# External_Trigger_Buffer.net
KiCad netlist of a schematic drawn in Altium Designer
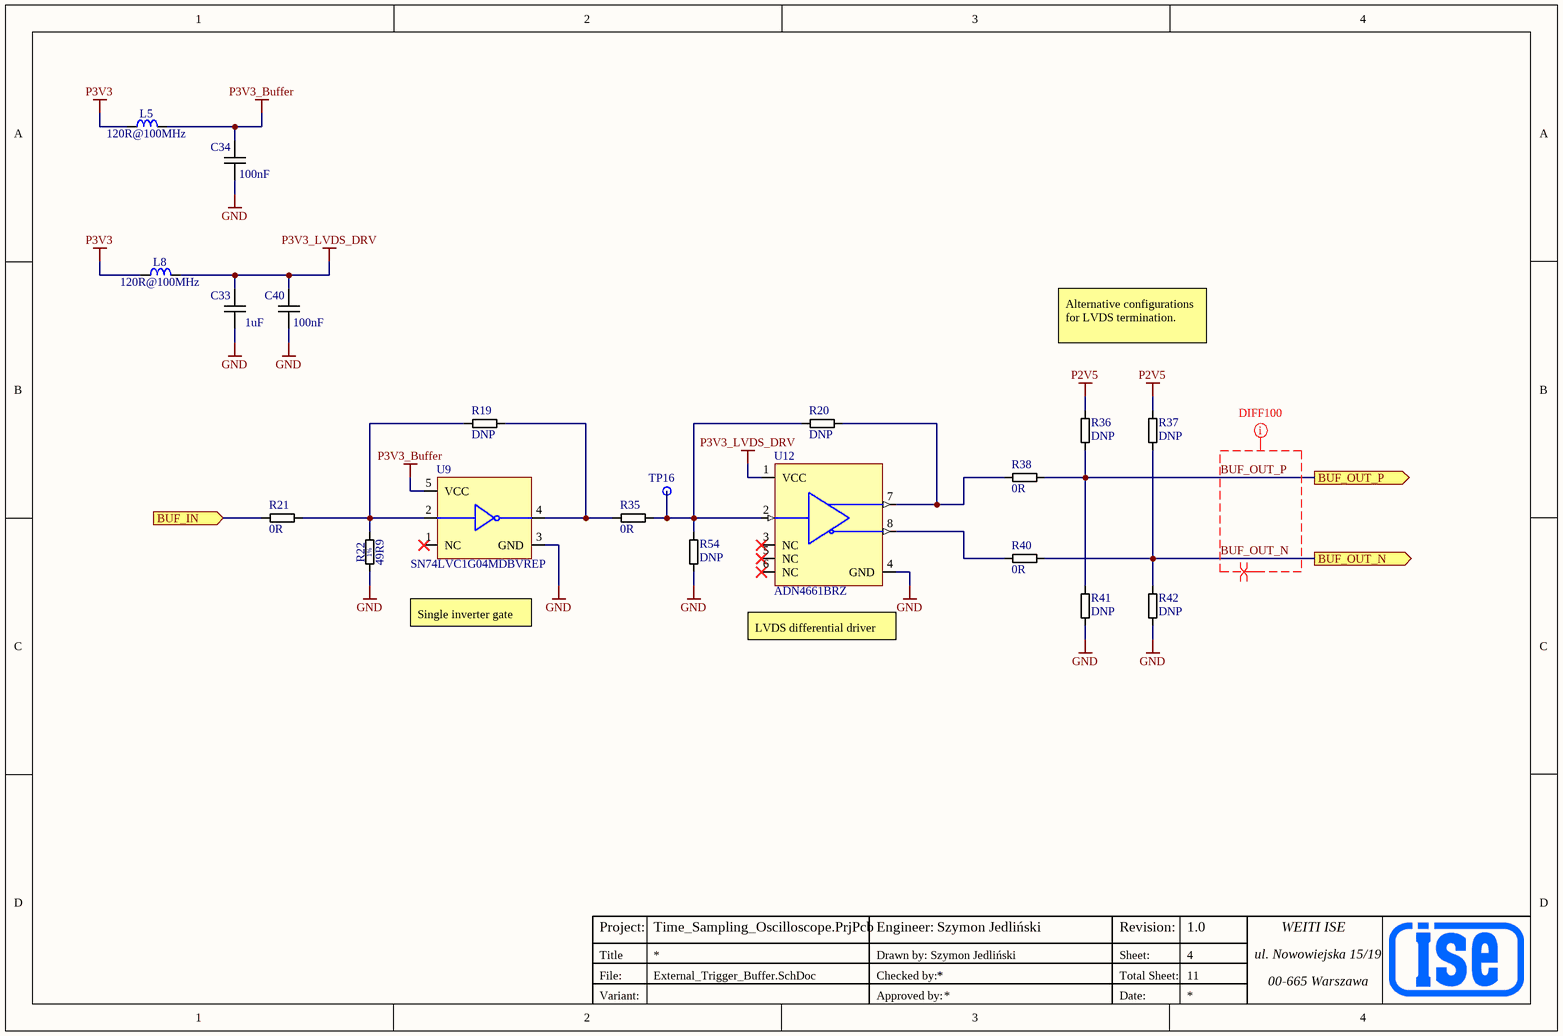
[diagram p0: External_Trigger_Buffer.SchDoc]

(export (version "E")
  (design (tool "Eeschema 10.0.6"))
  (components
    (comp (ref "C33")
      (value "1uF")
      (footprint "CAPC0603X90N")
      (description "Non-polarised capacitor")
      (fields (field (name "MANUFACTURER PART NUMBER") "CL10B105KO8NNNC"))
      (libsource (lib "Capacitors") (part "Capacitor - non polarized"))
    )
    (comp (ref "C34")
      (value "100nF")
      (footprint "CAPC0603X90N")
      (description "Non-polarised capacitor")
      (fields (field (name "MANUFACTURER PART NUMBER") "VJ0603Y104KXJCW1BC"))
      (libsource (lib "Capacitors") (part "Capacitor - non polarized"))
    )
    (comp (ref "C40")
      (value "100nF")
      (footprint "CAPC0603X90N")
      (description "Non-polarised capacitor")
      (fields (field (name "MANUFACTURER PART NUMBER") "VJ0603Y104KXJCW1BC"))
      (libsource (lib "Capacitors") (part "Capacitor - non polarized"))
    )
    (comp (ref "L5")
      (value "120R@100MHz")
      (footprint "INDC0603X90N")
      (description "Ferrite Bead")
      (fields (field (name "MANUFACTURER PART NUMBER") "BLM18PG121SN1D") (field (name "TOLERANCE") "25%"))
      (libsource (lib "Inductors") (part "Inductor"))
    )
    (comp (ref "L8")
      (value "120R@100MHz")
      (footprint "INDC0603X90N")
      (description "Ferrite Bead")
      (fields (field (name "MANUFACTURER PART NUMBER") "BLM18PG121SN1D") (field (name "TOLERANCE") "25%"))
      (libsource (lib "Inductors") (part "Inductor"))
    )
    (comp (ref "R19")
      (value "DNP")
      (footprint "RESC0402X40N")
      (description "General Purpose Thick Film Chip Resistor")
      (fields (field (name "VOLTAGE") "50V"))
      (libsource (lib "Resistors") (part "Resistor - Generic"))
    )
    (comp (ref "R20")
      (value "DNP")
      (footprint "RESC0402X40N")
      (description "General Purpose Thick Film Chip Resistor")
      (fields (field (name "VOLTAGE") "50V"))
      (libsource (lib "Resistors") (part "Resistor - Generic"))
    )
    (comp (ref "R21")
      (value "0R")
      (footprint "RESC0402X40N")
      (description "General Purpose Thick Film Chip Resistor")
      (fields
        (field (name "MANUFACTURER PART NUMBER") "CRCW04020000Z0EDC")
        (field (name "TOLERANCE") "20mOhm")
      )
      (libsource (lib "Resistors") (part "Resistor - Generic"))
    )
    (comp (ref "R22")
      (value "49R9")
      (footprint "RESC0402X40N")
      (description "General Purpose Thick Film Chip Resistor")
      (fields (field (name "MANUFACTURER PART NUMBER") "RC0402FR-0749R9L") (field (name "TOLERANCE") "1%"))
      (libsource (lib "Resistors") (part "Resistor - 1%"))
    )
    (comp (ref "R35")
      (value "0R")
      (footprint "RESC0402X40N")
      (description "General Purpose Thick Film Chip Resistor")
      (fields
        (field (name "MANUFACTURER PART NUMBER") "CRCW04020000Z0EDC")
        (field (name "TOLERANCE") "20mOhm")
      )
      (libsource (lib "Resistors") (part "Resistor - Generic"))
    )
    (comp (ref "R36")
      (value "DNP")
      (footprint "RESC0402X40N")
      (description "General Purpose Thick Film Chip Resistor")
      (fields (field (name "VOLTAGE") "50V"))
      (libsource (lib "Resistors") (part "Resistor - Generic"))
    )
    (comp (ref "R37")
      (value "DNP")
      (footprint "RESC0402X40N")
      (description "General Purpose Thick Film Chip Resistor")
      (fields (field (name "VOLTAGE") "50V"))
      (libsource (lib "Resistors") (part "Resistor - Generic"))
    )
    (comp (ref "R38")
      (value "0R")
      (footprint "RESC0402X40N")
      (description "General Purpose Thick Film Chip Resistor")
      (fields
        (field (name "MANUFACTURER PART NUMBER") "CRCW04020000Z0EDC")
        (field (name "TOLERANCE") "20mOhm")
      )
      (libsource (lib "Resistors") (part "Resistor - Generic"))
    )
    (comp (ref "R40")
      (value "0R")
      (footprint "RESC0402X40N")
      (description "General Purpose Thick Film Chip Resistor")
      (fields
        (field (name "MANUFACTURER PART NUMBER") "CRCW04020000Z0EDC")
        (field (name "TOLERANCE") "20mOhm")
      )
      (libsource (lib "Resistors") (part "Resistor - Generic"))
    )
    (comp (ref "R41")
      (value "DNP")
      (footprint "RESC0402X40N")
      (description "General Purpose Thick Film Chip Resistor")
      (fields (field (name "VOLTAGE") "50V"))
      (libsource (lib "Resistors") (part "Resistor - Generic"))
    )
    (comp (ref "R42")
      (value "DNP")
      (footprint "RESC0402X40N")
      (description "General Purpose Thick Film Chip Resistor")
      (fields (field (name "VOLTAGE") "50V"))
      (libsource (lib "Resistors") (part "Resistor - Generic"))
    )
    (comp (ref "R54")
      (value "DNP")
      (footprint "RESC0402X40N")
      (description "General Purpose Thick Film Chip Resistor")
      (fields (field (name "VOLTAGE") "50V"))
      (libsource (lib "Resistors") (part "Resistor - Generic"))
    )
    (comp (ref "TP16")
      (value "TestPoint")
      (footprint "TESTPOINT_SMD_C1P27MM")
      (description "1.27mm diameter SMD Test Point Area")
      (libsource (lib "Mechanical_and_PCB_Features") (part "Test Point"))
    )
    (comp (ref "U9")
      (value "SN74LVC1G04MDBVREP")
      (footprint "SOT23-5")
      (description "SINGLE INVERTER GATE")
      (libsource (lib "ICs_and_Semiconductors") (part "SN74LVC1G04"))
    )
    (comp (ref "U12")
      (value "ADN4661BRZ")
      (footprint "SOIC-8")
      (description "ADN4661BRZ, Single, 3 V, CMOS, LVDS, High Speed Differential Driver")
      (libsource (lib "ICs_and_Semiconductors") (part "ADN4661BRZ"))
    )
  )
  (nets
    (net (code "1") (name "/BUF_IN") (class "Default")
      (node (ref "R21") (pin "1") (pinfunction "1_1") (pintype "passive"))
    )
    (net (code "2") (name "/BUF_OUT_N") (class "Default")
      (node (ref "R37") (pin "1") (pinfunction "1_1") (pintype "passive"))
      (node (ref "R40") (pin "2") (pinfunction "2_2") (pintype "passive"))
      (node (ref "R42") (pin "2") (pinfunction "2_2") (pintype "passive"))
    )
    (net (code "3") (name "/BUF_OUT_P") (class "Default")
      (node (ref "R36") (pin "1") (pinfunction "1_1") (pintype "passive"))
      (node (ref "R38") (pin "2") (pinfunction "2_2") (pintype "passive"))
      (node (ref "R41") (pin "2") (pinfunction "2_2") (pintype "passive"))
    )
    (net (code "4") (name "GND") (class "Default")
      (node (ref "C33") (pin "2") (pinfunction "2_2") (pintype "passive"))
      (node (ref "C34") (pin "2") (pinfunction "2_2") (pintype "passive"))
      (node (ref "C40") (pin "2") (pinfunction "2_2") (pintype "passive"))
      (node (ref "R22") (pin "1") (pinfunction "1_1") (pintype "passive"))
      (node (ref "R41") (pin "1") (pinfunction "1_1") (pintype "passive"))
      (node (ref "R42") (pin "1") (pinfunction "1_1") (pintype "passive"))
      (node (ref "R54") (pin "1") (pinfunction "1_1") (pintype "passive"))
      (node (ref "U12") (pin "4") (pinfunction "GND_4") (pintype "power_in"))
      (node (ref "U9") (pin "3") (pinfunction "GND_3") (pintype "passive"))
    )
    (net (code "5") (name "Net-(U9-A)") (class "Default")
      (node (ref "R19") (pin "2") (pinfunction "2_2") (pintype "passive"))
      (node (ref "R21") (pin "2") (pinfunction "2_2") (pintype "passive"))
      (node (ref "R22") (pin "2") (pinfunction "2_2") (pintype "passive"))
      (node (ref "U9") (pin "2") (pinfunction "A_2") (pintype "passive"))
    )
    (net (code "6") (name "Net-(U9-Y)") (class "Default")
      (node (ref "R19") (pin "1") (pinfunction "1_1") (pintype "passive"))
      (node (ref "R35") (pin "1") (pinfunction "1_1") (pintype "passive"))
      (node (ref "U9") (pin "4") (pinfunction "Y_4") (pintype "passive"))
    )
    (net (code "7") (name "Net-(U12-DIN)") (class "Default")
      (node (ref "R20") (pin "2") (pinfunction "2_2") (pintype "passive"))
      (node (ref "R35") (pin "2") (pinfunction "2_2") (pintype "passive"))
      (node (ref "R54") (pin "2") (pinfunction "2_2") (pintype "passive"))
      (node (ref "TP16") (pin "1") (pinfunction "1_1") (pintype "passive"))
      (node (ref "U12") (pin "2") (pinfunction "DIN_2") (pintype "input"))
    )
    (net (code "8") (name "Net-(U12-DOUT+)") (class "Default")
      (node (ref "R20") (pin "1") (pinfunction "1_1") (pintype "passive"))
      (node (ref "R38") (pin "1") (pinfunction "1_1") (pintype "passive"))
      (node (ref "U12") (pin "7") (pinfunction "DOUT+_7") (pintype "output"))
    )
    (net (code "9") (name "Net-(U12-DOUT-)") (class "Default")
      (node (ref "R40") (pin "1") (pinfunction "1_1") (pintype "passive"))
      (node (ref "U12") (pin "8") (pinfunction "DOUT-_8") (pintype "output"))
    )
    (net (code "10") (name "P2V5") (class "Default")
      (node (ref "R36") (pin "2") (pinfunction "2_2") (pintype "passive"))
      (node (ref "R37") (pin "2") (pinfunction "2_2") (pintype "passive"))
    )
    (net (code "11") (name "P3V3") (class "Default")
      (node (ref "L5") (pin "1") (pinfunction "1_1") (pintype "passive"))
      (node (ref "L8") (pin "1") (pinfunction "1_1") (pintype "passive"))
    )
    (net (code "12") (name "P3V3_Buffer") (class "Default")
      (node (ref "C34") (pin "1") (pinfunction "1_1") (pintype "passive"))
      (node (ref "L5") (pin "2") (pinfunction "2_2") (pintype "passive"))
      (node (ref "U9") (pin "5") (pinfunction "VCC_5") (pintype "passive"))
    )
    (net (code "13") (name "P3V3_LVDS_DRV") (class "Default")
      (node (ref "C33") (pin "1") (pinfunction "1_1") (pintype "passive"))
      (node (ref "C40") (pin "1") (pinfunction "1_1") (pintype "passive"))
      (node (ref "L8") (pin "2") (pinfunction "2_2") (pintype "passive"))
      (node (ref "U12") (pin "1") (pinfunction "VCC_1") (pintype "power_in"))
    )
    (net (code "14") (name "unconnected-(U9-NC-Pad1)") (class "Default")
      (node (ref "U9") (pin "1") (pinfunction "NC_1") (pintype "passive+no_connect"))
    )
    (net (code "15") (name "unconnected-(U12-NC-Pad3)") (class "Default")
      (node (ref "U12") (pin "3") (pinfunction "NC_3") (pintype "passive+no_connect"))
    )
    (net (code "16") (name "unconnected-(U12-NC-Pad5)") (class "Default")
      (node (ref "U12") (pin "5") (pinfunction "NC_5") (pintype "passive+no_connect"))
    )
    (net (code "17") (name "unconnected-(U12-NC-Pad6)") (class "Default")
      (node (ref "U12") (pin "6") (pinfunction "NC_6") (pintype "passive+no_connect"))
    )
  )
)
